# Phono-v1.net
KiCad netlist of a schematic drawn in EAGLE
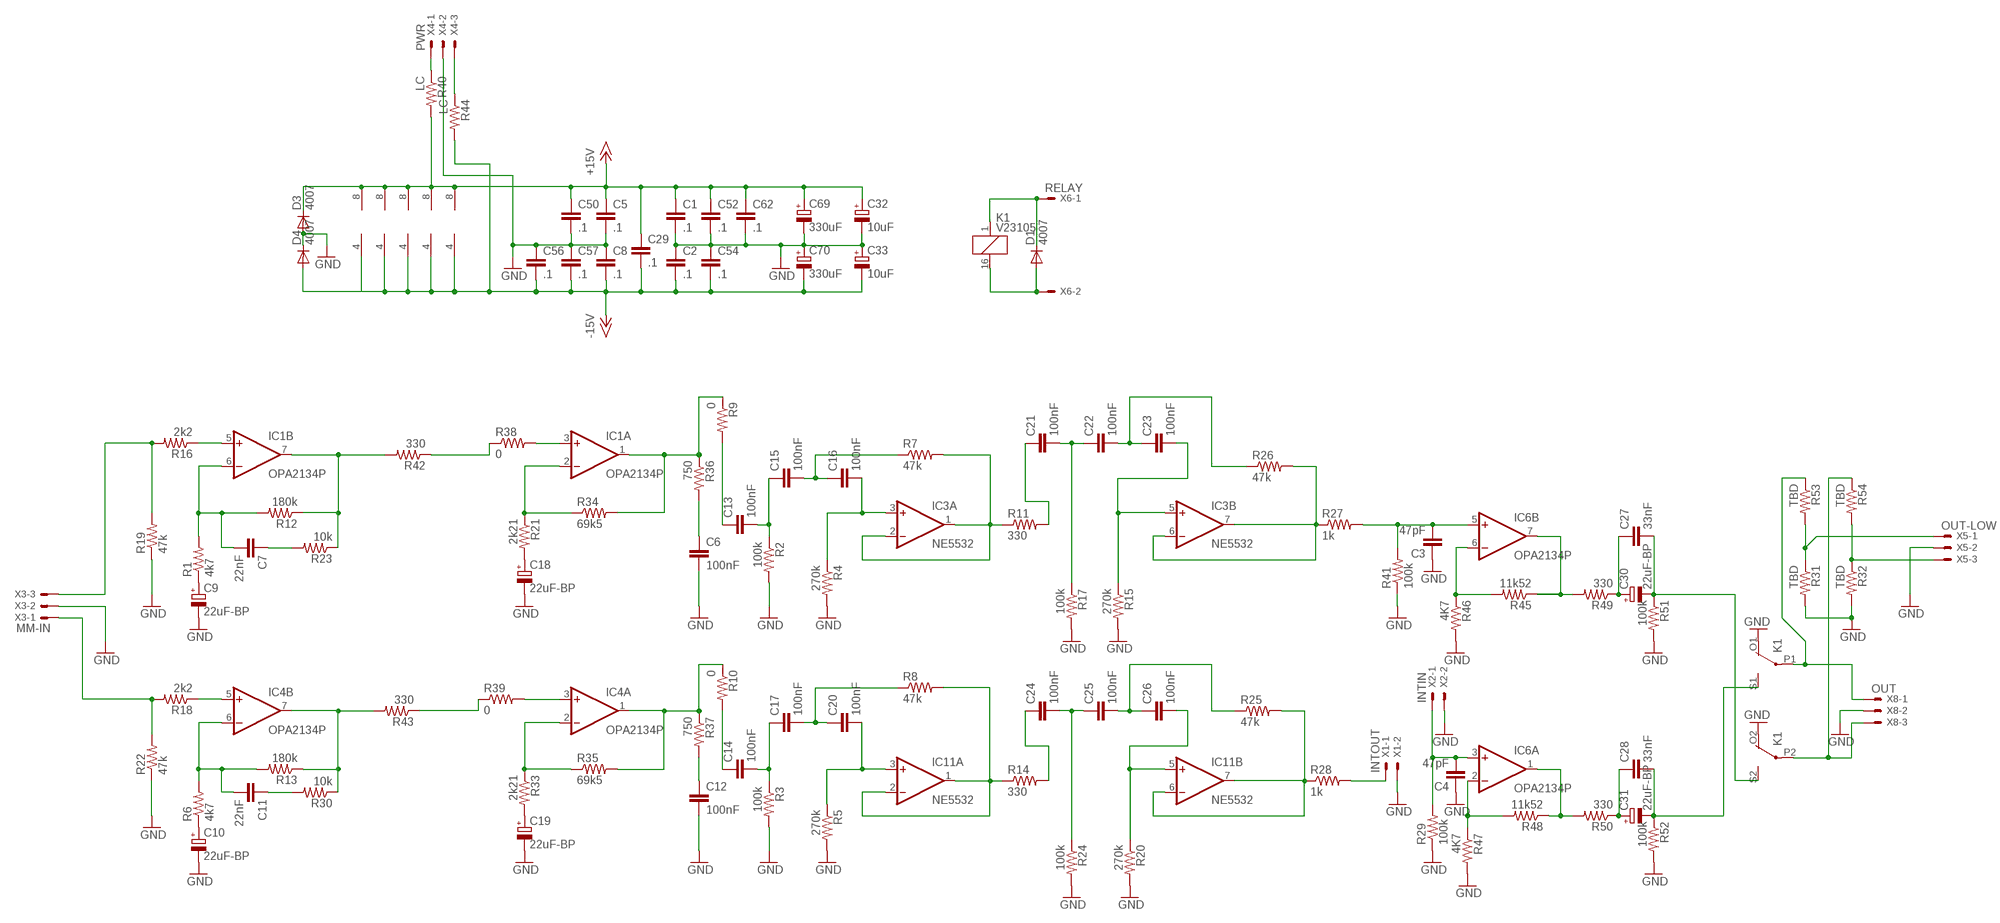
[diagram p0: schematic, sheet 1]

(export (version "E")
  (design (tool "Eeschema 10.0.6"))
  (components
    (comp (ref "C1")
      (value ".1")
      (footprint "eagle-import:C4532")
      (libsource (lib "eagle-import") (part "C-EUC4532"))
    )
    (comp (ref "C2")
      (value ".1")
      (footprint "eagle-import:C4532")
      (libsource (lib "eagle-import") (part "C-EUC4532"))
    )
    (comp (ref "C3")
      (value "47pF")
      (footprint "eagle-import:C1210")
      (libsource (lib "eagle-import") (part "C-EUC1210"))
    )
    (comp (ref "C4")
      (value "47pF")
      (footprint "eagle-import:C1210")
      (libsource (lib "eagle-import") (part "C-EUC1210"))
    )
    (comp (ref "C5")
      (value ".1")
      (footprint "eagle-import:C4532")
      (libsource (lib "eagle-import") (part "C-EUC4532"))
    )
    (comp (ref "C6")
      (value "100nF")
      (footprint "eagle-import:C050-075X075")
      (libsource (lib "eagle-import") (part "C-EU050-075X075"))
    )
    (comp (ref "C7")
      (value "22nF")
      (footprint "eagle-import:C050-075X075")
      (libsource (lib "eagle-import") (part "C-EU050-075X075"))
    )
    (comp (ref "C8")
      (value ".1")
      (footprint "eagle-import:C4532")
      (libsource (lib "eagle-import") (part "C-EUC4532"))
    )
    (comp (ref "C9")
      (value "22uF-BP")
      (footprint "eagle-import:E5-10,5")
      (libsource (lib "eagle-import") (part "CPOL-EUE5-10.5"))
    )
    (comp (ref "C10")
      (value "22uF-BP")
      (footprint "eagle-import:E5-10,5")
      (libsource (lib "eagle-import") (part "CPOL-EUE5-10.5"))
    )
    (comp (ref "C11")
      (value "22nF")
      (footprint "eagle-import:C050-075X075")
      (libsource (lib "eagle-import") (part "C-EU050-075X075"))
    )
    (comp (ref "C12")
      (value "100nF")
      (footprint "eagle-import:C050-075X075")
      (libsource (lib "eagle-import") (part "C-EU050-075X075"))
    )
    (comp (ref "C13")
      (value "100nF")
      (footprint "eagle-import:C050-075X075")
      (libsource (lib "eagle-import") (part "C-EU050-075X075"))
    )
    (comp (ref "C14")
      (value "100nF")
      (footprint "eagle-import:C050-075X075")
      (libsource (lib "eagle-import") (part "C-EU050-075X075"))
    )
    (comp (ref "C15")
      (value "100nF")
      (footprint "eagle-import:C050-075X075")
      (libsource (lib "eagle-import") (part "C-EU050-075X075"))
    )
    (comp (ref "C16")
      (value "100nF")
      (footprint "eagle-import:C050-075X075")
      (libsource (lib "eagle-import") (part "C-EU050-075X075"))
    )
    (comp (ref "C17")
      (value "100nF")
      (footprint "eagle-import:C050-075X075")
      (libsource (lib "eagle-import") (part "C-EU050-075X075"))
    )
    (comp (ref "C18")
      (value "22uF-BP")
      (footprint "eagle-import:E5-10,5")
      (libsource (lib "eagle-import") (part "CPOL-EUE5-10.5"))
    )
    (comp (ref "C19")
      (value "22uF-BP")
      (footprint "eagle-import:E5-10,5")
      (libsource (lib "eagle-import") (part "CPOL-EUE5-10.5"))
    )
    (comp (ref "C20")
      (value "100nF")
      (footprint "eagle-import:C050-075X075")
      (libsource (lib "eagle-import") (part "C-EU050-075X075"))
    )
    (comp (ref "C21")
      (value "100nF")
      (footprint "eagle-import:C050-075X075")
      (libsource (lib "eagle-import") (part "C-EU050-075X075"))
    )
    (comp (ref "C22")
      (value "100nF")
      (footprint "eagle-import:C050-075X075")
      (libsource (lib "eagle-import") (part "C-EU050-075X075"))
    )
    (comp (ref "C23")
      (value "100nF")
      (footprint "eagle-import:C050-075X075")
      (libsource (lib "eagle-import") (part "C-EU050-075X075"))
    )
    (comp (ref "C24")
      (value "100nF")
      (footprint "eagle-import:C050-075X075")
      (libsource (lib "eagle-import") (part "C-EU050-075X075"))
    )
    (comp (ref "C25")
      (value "100nF")
      (footprint "eagle-import:C050-075X075")
      (libsource (lib "eagle-import") (part "C-EU050-075X075"))
    )
    (comp (ref "C26")
      (value "100nF")
      (footprint "eagle-import:C050-075X075")
      (libsource (lib "eagle-import") (part "C-EU050-075X075"))
    )
    (comp (ref "C27")
      (value "33nF")
      (footprint "eagle-import:C050-075X075")
      (libsource (lib "eagle-import") (part "C-EU050-075X075"))
    )
    (comp (ref "C28")
      (value "33nF")
      (footprint "eagle-import:C050-075X075")
      (libsource (lib "eagle-import") (part "C-EU050-075X075"))
    )
    (comp (ref "C29")
      (value ".1")
      (footprint "eagle-import:C4532")
      (libsource (lib "eagle-import") (part "C-EUC4532"))
    )
    (comp (ref "C30")
      (value "22uF-BP")
      (footprint "eagle-import:E5-10,5")
      (libsource (lib "eagle-import") (part "CPOL-EUE5-10.5"))
    )
    (comp (ref "C31")
      (value "22uF-BP")
      (footprint "eagle-import:E5-10,5")
      (libsource (lib "eagle-import") (part "CPOL-EUE5-10.5"))
    )
    (comp (ref "C32")
      (value "10uF")
      (footprint "eagle-import:E2-5")
      (libsource (lib "eagle-import") (part "CPOL-EUE2-5"))
    )
    (comp (ref "C33")
      (value "10uF")
      (footprint "eagle-import:E2-5")
      (libsource (lib "eagle-import") (part "CPOL-EUE2-5"))
    )
    (comp (ref "C50")
      (value ".1")
      (footprint "eagle-import:C4532")
      (libsource (lib "eagle-import") (part "C-EUC4532"))
    )
    (comp (ref "C52")
      (value ".1")
      (footprint "eagle-import:C4532")
      (libsource (lib "eagle-import") (part "C-EUC4532"))
    )
    (comp (ref "C54")
      (value ".1")
      (footprint "eagle-import:C4532")
      (libsource (lib "eagle-import") (part "C-EUC4532"))
    )
    (comp (ref "C56")
      (value ".1")
      (footprint "eagle-import:C4532")
      (libsource (lib "eagle-import") (part "C-EUC4532"))
    )
    (comp (ref "C57")
      (value ".1")
      (footprint "eagle-import:C4532")
      (libsource (lib "eagle-import") (part "C-EUC4532"))
    )
    (comp (ref "C62")
      (value ".1")
      (footprint "eagle-import:C4532")
      (libsource (lib "eagle-import") (part "C-EUC4532"))
    )
    (comp (ref "C69")
      (value "330uF")
      (footprint "eagle-import:E5-10,5")
      (libsource (lib "eagle-import") (part "CPOL-EUE5-10.5"))
    )
    (comp (ref "C70")
      (value "330uF")
      (footprint "eagle-import:E5-10,5")
      (libsource (lib "eagle-import") (part "CPOL-EUE5-10.5"))
    )
    (comp (ref "D1")
      (value "4007")
      (footprint "eagle-import:DO35-7")
      (libsource (lib "eagle-import") (part "1N4148DO35-7"))
    )
    (comp (ref "D3")
      (value "4007")
      (footprint "eagle-import:DO35-10")
      (libsource (lib "eagle-import") (part "1N4148DO35-10"))
    )
    (comp (ref "D4")
      (value "4007")
      (footprint "eagle-import:DO35-10")
      (libsource (lib "eagle-import") (part "1N4148DO35-10"))
    )
    (comp (ref "IC1")
      (value "OPA2134P")
      (footprint "eagle-import:DIL08")
      (libsource (lib "eagle-import") (part "OPA2134P"))
    )
    (comp (ref "IC3")
      (value "NE5532")
      (footprint "eagle-import:DIL08")
      (libsource (lib "eagle-import") (part "OPA2134P"))
    )
    (comp (ref "IC4")
      (value "OPA2134P")
      (footprint "eagle-import:DIL08")
      (libsource (lib "eagle-import") (part "OPA2134P"))
    )
    (comp (ref "IC6")
      (value "OPA2134P")
      (footprint "eagle-import:DIL08")
      (libsource (lib "eagle-import") (part "OPA2134P"))
    )
    (comp (ref "IC11")
      (value "NE5532")
      (footprint "eagle-import:DIL08")
      (libsource (lib "eagle-import") (part "OPA2134P"))
    )
    (comp (ref "K1")
      (value "V23105")
      (footprint "eagle-import:351")
      (libsource (lib "eagle-import") (part "351"))
    )
    (comp (ref "R1")
      (value "4k7")
      (footprint "eagle-import:0309_10")
      (libsource (lib "eagle-import") (part "R-US_0309/10"))
    )
    (comp (ref "R2")
      (value "100k")
      (footprint "eagle-import:0309_10")
      (libsource (lib "eagle-import") (part "R-US_0309/10"))
    )
    (comp (ref "R3")
      (value "100k")
      (footprint "eagle-import:0309_10")
      (libsource (lib "eagle-import") (part "R-US_0309/10"))
    )
    (comp (ref "R4")
      (value "270k")
      (footprint "eagle-import:0309_10")
      (libsource (lib "eagle-import") (part "R-US_0309/10"))
    )
    (comp (ref "R5")
      (value "270k")
      (footprint "eagle-import:0309_10")
      (libsource (lib "eagle-import") (part "R-US_0309/10"))
    )
    (comp (ref "R6")
      (value "4k7")
      (footprint "eagle-import:0309_10")
      (libsource (lib "eagle-import") (part "R-US_0309/10"))
    )
    (comp (ref "R7")
      (value "47k")
      (footprint "eagle-import:0309_10")
      (libsource (lib "eagle-import") (part "R-US_0309/10"))
    )
    (comp (ref "R8")
      (value "47k")
      (footprint "eagle-import:0309_10")
      (libsource (lib "eagle-import") (part "R-US_0309/10"))
    )
    (comp (ref "R9")
      (value "0")
      (footprint "eagle-import:0309_10")
      (libsource (lib "eagle-import") (part "R-US_0309/10"))
    )
    (comp (ref "R10")
      (value "0")
      (footprint "eagle-import:0309_12")
      (libsource (lib "eagle-import") (part "R-US_0309/12"))
    )
    (comp (ref "R11")
      (value "330")
      (footprint "eagle-import:0309_10")
      (libsource (lib "eagle-import") (part "R-US_0309/10"))
    )
    (comp (ref "R12")
      (value "180k")
      (footprint "eagle-import:0309_10")
      (libsource (lib "eagle-import") (part "R-US_0309/10"))
    )
    (comp (ref "R13")
      (value "180k")
      (footprint "eagle-import:0309_10")
      (libsource (lib "eagle-import") (part "R-US_0309/10"))
    )
    (comp (ref "R14")
      (value "330")
      (footprint "eagle-import:0309_10")
      (libsource (lib "eagle-import") (part "R-US_0309/10"))
    )
    (comp (ref "R15")
      (value "270k")
      (footprint "eagle-import:0309_10")
      (libsource (lib "eagle-import") (part "R-US_0309/10"))
    )
    (comp (ref "R16")
      (value "2k2")
      (footprint "eagle-import:0309_10")
      (libsource (lib "eagle-import") (part "R-US_0309/10"))
    )
    (comp (ref "R17")
      (value "100k")
      (footprint "eagle-import:0309_10")
      (libsource (lib "eagle-import") (part "R-US_0309/10"))
    )
    (comp (ref "R18")
      (value "2k2")
      (footprint "eagle-import:0309_10")
      (libsource (lib "eagle-import") (part "R-US_0309/10"))
    )
    (comp (ref "R19")
      (value "47k")
      (footprint "eagle-import:0309_10")
      (libsource (lib "eagle-import") (part "R-US_0309/10"))
    )
    (comp (ref "R20")
      (value "270k")
      (footprint "eagle-import:0309_10")
      (libsource (lib "eagle-import") (part "R-US_0309/10"))
    )
    (comp (ref "R21")
      (value "2k21")
      (footprint "eagle-import:0309_10")
      (libsource (lib "eagle-import") (part "R-US_0309/10"))
    )
    (comp (ref "R22")
      (value "47k")
      (footprint "eagle-import:0309_10")
      (libsource (lib "eagle-import") (part "R-US_0309/10"))
    )
    (comp (ref "R23")
      (value "10k")
      (footprint "eagle-import:0309_10")
      (libsource (lib "eagle-import") (part "R-US_0309/10"))
    )
    (comp (ref "R24")
      (value "100k")
      (footprint "eagle-import:0309_10")
      (libsource (lib "eagle-import") (part "R-US_0309/10"))
    )
    (comp (ref "R25")
      (value "47k")
      (footprint "eagle-import:0309_10")
      (libsource (lib "eagle-import") (part "R-US_0309/10"))
    )
    (comp (ref "R26")
      (value "47k")
      (footprint "eagle-import:0309_10")
      (libsource (lib "eagle-import") (part "R-US_0309/10"))
    )
    (comp (ref "R27")
      (value "1k")
      (footprint "eagle-import:0309_10")
      (libsource (lib "eagle-import") (part "R-US_0309/10"))
    )
    (comp (ref "R28")
      (value "1k")
      (footprint "eagle-import:0309_12")
      (libsource (lib "eagle-import") (part "R-US_0309/12"))
    )
    (comp (ref "R29")
      (value "100k")
      (footprint "eagle-import:0309_10")
      (libsource (lib "eagle-import") (part "R-US_0309/10"))
    )
    (comp (ref "R30")
      (value "10k")
      (footprint "eagle-import:0309_10")
      (libsource (lib "eagle-import") (part "R-US_0309/10"))
    )
    (comp (ref "R31")
      (value "TBD")
      (footprint "eagle-import:0309_10")
      (libsource (lib "eagle-import") (part "R-US_0309/10"))
    )
    (comp (ref "R32")
      (value "TBD")
      (footprint "eagle-import:0309_10")
      (libsource (lib "eagle-import") (part "R-US_0309/10"))
    )
    (comp (ref "R33")
      (value "2k21")
      (footprint "eagle-import:0309_10")
      (libsource (lib "eagle-import") (part "R-US_0309/10"))
    )
    (comp (ref "R34")
      (value "69k5")
      (footprint "eagle-import:0309_10")
      (libsource (lib "eagle-import") (part "R-US_0309/10"))
    )
    (comp (ref "R35")
      (value "69k5")
      (footprint "eagle-import:0309_10")
      (libsource (lib "eagle-import") (part "R-US_0309/10"))
    )
    (comp (ref "R36")
      (value "750")
      (footprint "eagle-import:0309_10")
      (libsource (lib "eagle-import") (part "R-US_0309/10"))
    )
    (comp (ref "R37")
      (value "750")
      (footprint "eagle-import:0309_10")
      (libsource (lib "eagle-import") (part "R-US_0309/10"))
    )
    (comp (ref "R38")
      (value "0")
      (footprint "eagle-import:0207_7")
      (libsource (lib "eagle-import") (part "R-US_0207/7"))
    )
    (comp (ref "R39")
      (value "0")
      (footprint "eagle-import:0204_7")
      (libsource (lib "eagle-import") (part "R-US_0204/7"))
    )
    (comp (ref "R40")
      (value "LC")
      (footprint "eagle-import:0309_12")
      (libsource (lib "eagle-import") (part "R-US_0309/12"))
    )
    (comp (ref "R41")
      (value "100k")
      (footprint "eagle-import:0309_10")
      (libsource (lib "eagle-import") (part "R-US_0309/10"))
    )
    (comp (ref "R42")
      (value "330")
      (footprint "eagle-import:0309_10")
      (libsource (lib "eagle-import") (part "R-US_0309/10"))
    )
    (comp (ref "R43")
      (value "330")
      (footprint "eagle-import:0309_10")
      (libsource (lib "eagle-import") (part "R-US_0309/10"))
    )
    (comp (ref "R44")
      (value "LC")
      (footprint "eagle-import:0309_12")
      (libsource (lib "eagle-import") (part "R-US_0309/12"))
    )
    (comp (ref "R45")
      (value "11k52")
      (footprint "eagle-import:0309_10")
      (libsource (lib "eagle-import") (part "R-US_0309/10"))
    )
    (comp (ref "R46")
      (value "4K7")
      (footprint "eagle-import:0309_10")
      (libsource (lib "eagle-import") (part "R-US_0309/10"))
    )
    (comp (ref "R47")
      (value "4K7")
      (footprint "eagle-import:0309_10")
      (libsource (lib "eagle-import") (part "R-US_0309/10"))
    )
    (comp (ref "R48")
      (value "11k52")
      (footprint "eagle-import:0309_10")
      (libsource (lib "eagle-import") (part "R-US_0309/10"))
    )
    (comp (ref "R49")
      (value "330")
      (footprint "eagle-import:0309_10")
      (libsource (lib "eagle-import") (part "R-US_0309/10"))
    )
    (comp (ref "R50")
      (value "330")
      (footprint "eagle-import:0309_10")
      (libsource (lib "eagle-import") (part "R-US_0309/10"))
    )
    (comp (ref "R51")
      (value "100k")
      (footprint "eagle-import:0309_10")
      (libsource (lib "eagle-import") (part "R-US_0309/10"))
    )
    (comp (ref "R52")
      (value "100k")
      (footprint "eagle-import:0309_10")
      (libsource (lib "eagle-import") (part "R-US_0309/10"))
    )
    (comp (ref "R53")
      (value "TBD")
      (footprint "eagle-import:0309_10")
      (libsource (lib "eagle-import") (part "R-US_0309/10"))
    )
    (comp (ref "R54")
      (value "TBD")
      (footprint "eagle-import:0309_10")
      (libsource (lib "eagle-import") (part "R-US_0309/10"))
    )
    (comp (ref "X1")
      (value "INTOUT")
      (footprint "eagle-import:22-23-2021")
      (fields (field (name "MF") "MOLEX") (field (name "MPN") "22-23-2021"))
      (libsource (lib "eagle-import") (part "22-23-2021"))
    )
    (comp (ref "X2")
      (value "INTIN")
      (footprint "eagle-import:22-23-2021")
      (fields (field (name "MF") "MOLEX") (field (name "MPN") "22-23-2021"))
      (libsource (lib "eagle-import") (part "22-23-2021"))
    )
    (comp (ref "X3")
      (value "MM-IN")
      (footprint "eagle-import:22-23-2031")
      (fields (field (name "MF") "MOLEX") (field (name "MPN") "22-23-2031"))
      (libsource (lib "eagle-import") (part "22-23-2031"))
    )
    (comp (ref "X4")
      (value "PWR")
      (footprint "eagle-import:22-23-2031")
      (fields (field (name "MF") "MOLEX") (field (name "MPN") "22-23-2031"))
      (libsource (lib "eagle-import") (part "22-23-2031"))
    )
    (comp (ref "X5")
      (value "OUT-LOW")
      (footprint "eagle-import:22-23-2031")
      (fields (field (name "MF") "MOLEX") (field (name "MPN") "22-23-2031"))
      (libsource (lib "eagle-import") (part "22-23-2031"))
    )
    (comp (ref "X6")
      (value "RELAY")
      (footprint "eagle-import:22-23-2021")
      (fields (field (name "MF") "MOLEX") (field (name "MPN") "22-23-2021"))
      (libsource (lib "eagle-import") (part "22-23-2021"))
    )
    (comp (ref "X8")
      (value "OUT")
      (footprint "eagle-import:22-23-2031")
      (fields (field (name "MF") "MOLEX") (field (name "MPN") "22-23-2031"))
      (libsource (lib "eagle-import") (part "22-23-2031"))
    )
  )
  (nets
    (net (code "1") (name "+15V") (class "Default")
      (node (ref "C1") (pin "1") (pinfunction "1_1") (pintype "passive"))
      (node (ref "C29") (pin "1") (pinfunction "1_1") (pintype "passive"))
      (node (ref "C32") (pin "+") (pinfunction "+_+") (pintype "passive"))
      (node (ref "C5") (pin "1") (pinfunction "1_1") (pintype "passive"))
      (node (ref "C50") (pin "1") (pinfunction "1_1") (pintype "passive"))
      (node (ref "C52") (pin "1") (pinfunction "1_1") (pintype "passive"))
      (node (ref "C62") (pin "1") (pinfunction "1_1") (pintype "passive"))
      (node (ref "C69") (pin "+") (pinfunction "+_+") (pintype "passive"))
      (node (ref "D3") (pin "C") (pinfunction "C_C") (pintype "passive"))
      (node (ref "IC1") (pin "8") (pinfunction "V+_8") (pintype "power_in"))
      (node (ref "IC11") (pin "8") (pinfunction "V+_8") (pintype "power_in"))
      (node (ref "IC3") (pin "8") (pinfunction "V+_8") (pintype "power_in"))
      (node (ref "IC4") (pin "8") (pinfunction "V+_8") (pintype "power_in"))
      (node (ref "IC6") (pin "8") (pinfunction "V+_8") (pintype "power_in"))
      (node (ref "R40") (pin "2") (pinfunction "2_2") (pintype "passive"))
    )
    (net (code "2") (name "-15V") (class "Default")
      (node (ref "C2") (pin "2") (pinfunction "2_2") (pintype "passive"))
      (node (ref "C29") (pin "2") (pinfunction "2_2") (pintype "passive"))
      (node (ref "C33") (pin "-") (pinfunction "-_-") (pintype "passive"))
      (node (ref "C54") (pin "2") (pinfunction "2_2") (pintype "passive"))
      (node (ref "C56") (pin "2") (pinfunction "2_2") (pintype "passive"))
      (node (ref "C57") (pin "2") (pinfunction "2_2") (pintype "passive"))
      (node (ref "C70") (pin "-") (pinfunction "-_-") (pintype "passive"))
      (node (ref "C8") (pin "2") (pinfunction "2_2") (pintype "passive"))
      (node (ref "D4") (pin "A") (pinfunction "A_A") (pintype "passive"))
      (node (ref "IC1") (pin "4") (pinfunction "V-_4") (pintype "power_in"))
      (node (ref "IC11") (pin "4") (pinfunction "V-_4") (pintype "power_in"))
      (node (ref "IC3") (pin "4") (pinfunction "V-_4") (pintype "power_in"))
      (node (ref "IC4") (pin "4") (pinfunction "V-_4") (pintype "power_in"))
      (node (ref "IC6") (pin "4") (pinfunction "V-_4") (pintype "power_in"))
      (node (ref "R44") (pin "2") (pinfunction "2_2") (pintype "passive"))
    )
    (net (code "3") (name "GND") (class "Default")
      (node (ref "C1") (pin "2") (pinfunction "2_2") (pintype "passive"))
      (node (ref "C10") (pin "-") (pinfunction "-_-") (pintype "passive"))
      (node (ref "C12") (pin "2") (pinfunction "2_2") (pintype "passive"))
      (node (ref "C18") (pin "-") (pinfunction "-_-") (pintype "passive"))
      (node (ref "C19") (pin "-") (pinfunction "-_-") (pintype "passive"))
      (node (ref "C2") (pin "1") (pinfunction "1_1") (pintype "passive"))
      (node (ref "C3") (pin "1") (pinfunction "1_1") (pintype "passive"))
      (node (ref "C32") (pin "-") (pinfunction "-_-") (pintype "passive"))
      (node (ref "C33") (pin "+") (pinfunction "+_+") (pintype "passive"))
      (node (ref "C4") (pin "1") (pinfunction "1_1") (pintype "passive"))
      (node (ref "C5") (pin "2") (pinfunction "2_2") (pintype "passive"))
      (node (ref "C50") (pin "2") (pinfunction "2_2") (pintype "passive"))
      (node (ref "C52") (pin "2") (pinfunction "2_2") (pintype "passive"))
      (node (ref "C54") (pin "1") (pinfunction "1_1") (pintype "passive"))
      (node (ref "C56") (pin "1") (pinfunction "1_1") (pintype "passive"))
      (node (ref "C57") (pin "1") (pinfunction "1_1") (pintype "passive"))
      (node (ref "C6") (pin "2") (pinfunction "2_2") (pintype "passive"))
      (node (ref "C62") (pin "2") (pinfunction "2_2") (pintype "passive"))
      (node (ref "C69") (pin "-") (pinfunction "-_-") (pintype "passive"))
      (node (ref "C70") (pin "+") (pinfunction "+_+") (pintype "passive"))
      (node (ref "C8") (pin "1") (pinfunction "1_1") (pintype "passive"))
      (node (ref "C9") (pin "-") (pinfunction "-_-") (pintype "passive"))
      (node (ref "D3") (pin "A") (pinfunction "A_A") (pintype "passive"))
      (node (ref "D4") (pin "C") (pinfunction "C_C") (pintype "passive"))
      (node (ref "K1") (pin "O1") (pinfunction "O_O1") (pintype "passive"))
      (node (ref "K1") (pin "O2") (pinfunction "O_O2") (pintype "passive"))
      (node (ref "R15") (pin "2") (pinfunction "2_2") (pintype "passive"))
      (node (ref "R17") (pin "2") (pinfunction "2_2") (pintype "passive"))
      (node (ref "R19") (pin "1") (pinfunction "1_1") (pintype "passive"))
      (node (ref "R2") (pin "2") (pinfunction "2_2") (pintype "passive"))
      (node (ref "R20") (pin "2") (pinfunction "2_2") (pintype "passive"))
      (node (ref "R22") (pin "1") (pinfunction "1_1") (pintype "passive"))
      (node (ref "R24") (pin "2") (pinfunction "2_2") (pintype "passive"))
      (node (ref "R29") (pin "1") (pinfunction "1_1") (pintype "passive"))
      (node (ref "R3") (pin "2") (pinfunction "2_2") (pintype "passive"))
      (node (ref "R31") (pin "2") (pinfunction "2_2") (pintype "passive"))
      (node (ref "R32") (pin "2") (pinfunction "2_2") (pintype "passive"))
      (node (ref "R4") (pin "2") (pinfunction "2_2") (pintype "passive"))
      (node (ref "R41") (pin "1") (pinfunction "1_1") (pintype "passive"))
      (node (ref "R46") (pin "2") (pinfunction "2_2") (pintype "passive"))
      (node (ref "R47") (pin "2") (pinfunction "2_2") (pintype "passive"))
      (node (ref "R5") (pin "2") (pinfunction "2_2") (pintype "passive"))
      (node (ref "R51") (pin "2") (pinfunction "2_2") (pintype "passive"))
      (node (ref "R52") (pin "2") (pinfunction "2_2") (pintype "passive"))
      (node (ref "X1") (pin "2") (pinfunction "S_2") (pintype "passive"))
      (node (ref "X2") (pin "2") (pinfunction "S_2") (pintype "passive"))
      (node (ref "X3") (pin "2") (pinfunction "S_2") (pintype "passive"))
      (node (ref "X4") (pin "2") (pinfunction "S_2") (pintype "passive"))
      (node (ref "X5") (pin "2") (pinfunction "S_2") (pintype "passive"))
      (node (ref "X8") (pin "2") (pinfunction "S_2") (pintype "passive"))
    )
    (net (code "4") (name "Net-(C6-Pad1)") (class "Default")
      (node (ref "C6") (pin "1") (pinfunction "1_1") (pintype "passive"))
      (node (ref "R36") (pin "2") (pinfunction "2_2") (pintype "passive"))
    )
    (net (code "5") (name "Net-(C7-Pad1)") (class "Default")
      (node (ref "C7") (pin "1") (pinfunction "1_1") (pintype "passive"))
      (node (ref "R23") (pin "2") (pinfunction "2_2") (pintype "passive"))
    )
    (net (code "6") (name "Net-(C9-Pad+)") (class "Default")
      (node (ref "C9") (pin "+") (pinfunction "+_+") (pintype "passive"))
      (node (ref "R1") (pin "1") (pinfunction "1_1") (pintype "passive"))
    )
    (net (code "7") (name "Net-(C10-Pad+)") (class "Default")
      (node (ref "C10") (pin "+") (pinfunction "+_+") (pintype "passive"))
      (node (ref "R6") (pin "1") (pinfunction "1_1") (pintype "passive"))
    )
    (net (code "8") (name "Net-(C11-Pad1)") (class "Default")
      (node (ref "C11") (pin "1") (pinfunction "1_1") (pintype "passive"))
      (node (ref "R30") (pin "2") (pinfunction "2_2") (pintype "passive"))
    )
    (net (code "9") (name "Net-(C12-Pad1)") (class "Default")
      (node (ref "C12") (pin "1") (pinfunction "1_1") (pintype "passive"))
      (node (ref "R37") (pin "2") (pinfunction "2_2") (pintype "passive"))
    )
    (net (code "10") (name "Net-(C13-Pad1)") (class "Default")
      (node (ref "C13") (pin "1") (pinfunction "1_1") (pintype "passive"))
      (node (ref "R9") (pin "2") (pinfunction "2_2") (pintype "passive"))
    )
    (net (code "11") (name "Net-(C13-Pad2)") (class "Default")
      (node (ref "C13") (pin "2") (pinfunction "2_2") (pintype "passive"))
      (node (ref "C15") (pin "1") (pinfunction "1_1") (pintype "passive"))
      (node (ref "R2") (pin "1") (pinfunction "1_1") (pintype "passive"))
    )
    (net (code "12") (name "Net-(C14-Pad1)") (class "Default")
      (node (ref "C14") (pin "1") (pinfunction "1_1") (pintype "passive"))
      (node (ref "R10") (pin "2") (pinfunction "2_2") (pintype "passive"))
    )
    (net (code "13") (name "Net-(C14-Pad2)") (class "Default")
      (node (ref "C14") (pin "2") (pinfunction "2_2") (pintype "passive"))
      (node (ref "C17") (pin "1") (pinfunction "1_1") (pintype "passive"))
      (node (ref "R3") (pin "1") (pinfunction "1_1") (pintype "passive"))
    )
    (net (code "14") (name "Net-(C15-Pad2)") (class "Default")
      (node (ref "C15") (pin "2") (pinfunction "2_2") (pintype "passive"))
      (node (ref "C16") (pin "1") (pinfunction "1_1") (pintype "passive"))
      (node (ref "R7") (pin "1") (pinfunction "1_1") (pintype "passive"))
    )
    (net (code "15") (name "Net-(C17-Pad2)") (class "Default")
      (node (ref "C17") (pin "2") (pinfunction "2_2") (pintype "passive"))
      (node (ref "C20") (pin "1") (pinfunction "1_1") (pintype "passive"))
      (node (ref "R8") (pin "1") (pinfunction "1_1") (pintype "passive"))
    )
    (net (code "16") (name "Net-(C18-Pad+)") (class "Default")
      (node (ref "C18") (pin "+") (pinfunction "+_+") (pintype "passive"))
      (node (ref "R21") (pin "2") (pinfunction "2_2") (pintype "passive"))
    )
    (net (code "17") (name "Net-(C19-Pad+)") (class "Default")
      (node (ref "C19") (pin "+") (pinfunction "+_+") (pintype "passive"))
      (node (ref "R33") (pin "2") (pinfunction "2_2") (pintype "passive"))
    )
    (net (code "18") (name "Net-(C21-Pad1)") (class "Default")
      (node (ref "C21") (pin "1") (pinfunction "1_1") (pintype "passive"))
      (node (ref "R11") (pin "2") (pinfunction "2_2") (pintype "passive"))
    )
    (net (code "19") (name "Net-(C21-Pad2)") (class "Default")
      (node (ref "C21") (pin "2") (pinfunction "2_2") (pintype "passive"))
      (node (ref "C22") (pin "1") (pinfunction "1_1") (pintype "passive"))
      (node (ref "R17") (pin "1") (pinfunction "1_1") (pintype "passive"))
    )
    (net (code "20") (name "Net-(C22-Pad2)") (class "Default")
      (node (ref "C22") (pin "2") (pinfunction "2_2") (pintype "passive"))
      (node (ref "C23") (pin "1") (pinfunction "1_1") (pintype "passive"))
      (node (ref "R26") (pin "1") (pinfunction "1_1") (pintype "passive"))
    )
    (net (code "21") (name "Net-(C24-Pad1)") (class "Default")
      (node (ref "C24") (pin "1") (pinfunction "1_1") (pintype "passive"))
      (node (ref "R14") (pin "2") (pinfunction "2_2") (pintype "passive"))
    )
    (net (code "22") (name "Net-(C24-Pad2)") (class "Default")
      (node (ref "C24") (pin "2") (pinfunction "2_2") (pintype "passive"))
      (node (ref "C25") (pin "1") (pinfunction "1_1") (pintype "passive"))
      (node (ref "R24") (pin "1") (pinfunction "1_1") (pintype "passive"))
    )
    (net (code "23") (name "Net-(C25-Pad2)") (class "Default")
      (node (ref "C25") (pin "2") (pinfunction "2_2") (pintype "passive"))
      (node (ref "C26") (pin "1") (pinfunction "1_1") (pintype "passive"))
      (node (ref "R25") (pin "1") (pinfunction "1_1") (pintype "passive"))
    )
    (net (code "24") (name "Net-(C27-Pad1)") (class "Default")
      (node (ref "C27") (pin "1") (pinfunction "1_1") (pintype "passive"))
      (node (ref "C30") (pin "+") (pinfunction "+_+") (pintype "passive"))
      (node (ref "R49") (pin "1") (pinfunction "1_1") (pintype "passive"))
    )
    (net (code "25") (name "Net-(C28-Pad1)") (class "Default")
      (node (ref "C28") (pin "1") (pinfunction "1_1") (pintype "passive"))
      (node (ref "C31") (pin "+") (pinfunction "+_+") (pintype "passive"))
      (node (ref "R50") (pin "1") (pinfunction "1_1") (pintype "passive"))
    )
    (net (code "26") (name "Net-(IC1A-+IN)") (class "Default")
      (node (ref "IC1") (pin "3") (pinfunction "+IN_3") (pintype "input"))
      (node (ref "R38") (pin "2") (pinfunction "2_2") (pintype "passive"))
    )
    (net (code "27") (name "Net-(IC1A--IN)") (class "Default")
      (node (ref "IC1") (pin "2") (pinfunction "-IN_2") (pintype "input"))
      (node (ref "R21") (pin "1") (pinfunction "1_1") (pintype "passive"))
      (node (ref "R34") (pin "1") (pinfunction "1_1") (pintype "passive"))
    )
    (net (code "28") (name "Net-(IC1A-OUT)") (class "Default")
      (node (ref "IC1") (pin "1") (pinfunction "OUT_1") (pintype "output"))
      (node (ref "R34") (pin "2") (pinfunction "2_2") (pintype "passive"))
      (node (ref "R36") (pin "1") (pinfunction "1_1") (pintype "passive"))
      (node (ref "R9") (pin "1") (pinfunction "1_1") (pintype "passive"))
    )
    (net (code "29") (name "Net-(IC1B-+IN)") (class "Default")
      (node (ref "IC1") (pin "5") (pinfunction "+IN_5") (pintype "input"))
      (node (ref "R16") (pin "1") (pinfunction "1_1") (pintype "passive"))
    )
    (net (code "30") (name "Net-(IC1B--IN)") (class "Default")
      (node (ref "C7") (pin "2") (pinfunction "2_2") (pintype "passive"))
      (node (ref "IC1") (pin "6") (pinfunction "-IN_6") (pintype "input"))
      (node (ref "R1") (pin "2") (pinfunction "2_2") (pintype "passive"))
      (node (ref "R12") (pin "2") (pinfunction "2_2") (pintype "passive"))
    )
    (net (code "31") (name "Net-(IC1B-OUT)") (class "Default")
      (node (ref "IC1") (pin "7") (pinfunction "OUT_7") (pintype "output"))
      (node (ref "R12") (pin "1") (pinfunction "1_1") (pintype "passive"))
      (node (ref "R23") (pin "1") (pinfunction "1_1") (pintype "passive"))
      (node (ref "R42") (pin "2") (pinfunction "2_2") (pintype "passive"))
    )
    (net (code "32") (name "Net-(IC3A-+IN)") (class "Default")
      (node (ref "C16") (pin "2") (pinfunction "2_2") (pintype "passive"))
      (node (ref "IC3") (pin "3") (pinfunction "+IN_3") (pintype "input"))
      (node (ref "R4") (pin "1") (pinfunction "1_1") (pintype "passive"))
    )
    (net (code "33") (name "Net-(IC3A--IN)") (class "Default")
      (node (ref "IC3") (pin "1") (pinfunction "OUT_1") (pintype "output"))
      (node (ref "IC3") (pin "2") (pinfunction "-IN_2") (pintype "input"))
      (node (ref "R11") (pin "1") (pinfunction "1_1") (pintype "passive"))
      (node (ref "R7") (pin "2") (pinfunction "2_2") (pintype "passive"))
    )
    (net (code "34") (name "Net-(IC3B-+IN)") (class "Default")
      (node (ref "C23") (pin "2") (pinfunction "2_2") (pintype "passive"))
      (node (ref "IC3") (pin "5") (pinfunction "+IN_5") (pintype "input"))
      (node (ref "R15") (pin "1") (pinfunction "1_1") (pintype "passive"))
    )
    (net (code "35") (name "Net-(IC3B--IN)") (class "Default")
      (node (ref "IC3") (pin "6") (pinfunction "-IN_6") (pintype "input"))
      (node (ref "IC3") (pin "7") (pinfunction "OUT_7") (pintype "output"))
      (node (ref "R26") (pin "2") (pinfunction "2_2") (pintype "passive"))
      (node (ref "R27") (pin "1") (pinfunction "1_1") (pintype "passive"))
    )
    (net (code "36") (name "Net-(IC4A-+IN)") (class "Default")
      (node (ref "IC4") (pin "3") (pinfunction "+IN_3") (pintype "input"))
      (node (ref "R39") (pin "2") (pinfunction "2_2") (pintype "passive"))
    )
    (net (code "37") (name "Net-(IC4A--IN)") (class "Default")
      (node (ref "IC4") (pin "2") (pinfunction "-IN_2") (pintype "input"))
      (node (ref "R33") (pin "1") (pinfunction "1_1") (pintype "passive"))
      (node (ref "R35") (pin "1") (pinfunction "1_1") (pintype "passive"))
    )
    (net (code "38") (name "Net-(IC4A-OUT)") (class "Default")
      (node (ref "IC4") (pin "1") (pinfunction "OUT_1") (pintype "output"))
      (node (ref "R10") (pin "1") (pinfunction "1_1") (pintype "passive"))
      (node (ref "R35") (pin "2") (pinfunction "2_2") (pintype "passive"))
      (node (ref "R37") (pin "1") (pinfunction "1_1") (pintype "passive"))
    )
    (net (code "39") (name "Net-(IC4B-+IN)") (class "Default")
      (node (ref "IC4") (pin "5") (pinfunction "+IN_5") (pintype "input"))
      (node (ref "R18") (pin "1") (pinfunction "1_1") (pintype "passive"))
    )
    (net (code "40") (name "Net-(IC4B--IN)") (class "Default")
      (node (ref "C11") (pin "2") (pinfunction "2_2") (pintype "passive"))
      (node (ref "IC4") (pin "6") (pinfunction "-IN_6") (pintype "input"))
      (node (ref "R13") (pin "2") (pinfunction "2_2") (pintype "passive"))
      (node (ref "R6") (pin "2") (pinfunction "2_2") (pintype "passive"))
    )
    (net (code "41") (name "Net-(IC4B-OUT)") (class "Default")
      (node (ref "IC4") (pin "7") (pinfunction "OUT_7") (pintype "output"))
      (node (ref "R13") (pin "1") (pinfunction "1_1") (pintype "passive"))
      (node (ref "R30") (pin "1") (pinfunction "1_1") (pintype "passive"))
      (node (ref "R43") (pin "2") (pinfunction "2_2") (pintype "passive"))
    )
    (net (code "42") (name "Net-(IC6A-+IN)") (class "Default")
      (node (ref "C4") (pin "2") (pinfunction "2_2") (pintype "passive"))
      (node (ref "IC6") (pin "3") (pinfunction "+IN_3") (pintype "input"))
      (node (ref "R29") (pin "2") (pinfunction "2_2") (pintype "passive"))
      (node (ref "X2") (pin "1") (pinfunction "S_1") (pintype "passive"))
    )
    (net (code "43") (name "Net-(IC6A--IN)") (class "Default")
      (node (ref "IC6") (pin "2") (pinfunction "-IN_2") (pintype "input"))
      (node (ref "R47") (pin "1") (pinfunction "1_1") (pintype "passive"))
      (node (ref "R48") (pin "2") (pinfunction "2_2") (pintype "passive"))
    )
    (net (code "44") (name "Net-(IC6A-OUT)") (class "Default")
      (node (ref "IC6") (pin "1") (pinfunction "OUT_1") (pintype "output"))
      (node (ref "R48") (pin "1") (pinfunction "1_1") (pintype "passive"))
      (node (ref "R50") (pin "2") (pinfunction "2_2") (pintype "passive"))
    )
    (net (code "45") (name "Net-(IC6B-+IN)") (class "Default")
      (node (ref "C3") (pin "2") (pinfunction "2_2") (pintype "passive"))
      (node (ref "IC6") (pin "5") (pinfunction "+IN_5") (pintype "input"))
      (node (ref "R27") (pin "2") (pinfunction "2_2") (pintype "passive"))
      (node (ref "R41") (pin "2") (pinfunction "2_2") (pintype "passive"))
    )
    (net (code "46") (name "Net-(IC6B--IN)") (class "Default")
      (node (ref "IC6") (pin "6") (pinfunction "-IN_6") (pintype "input"))
      (node (ref "R45") (pin "2") (pinfunction "2_2") (pintype "passive"))
      (node (ref "R46") (pin "1") (pinfunction "1_1") (pintype "passive"))
    )
    (net (code "47") (name "Net-(IC6B-OUT)") (class "Default")
      (node (ref "IC6") (pin "7") (pinfunction "OUT_7") (pintype "output"))
      (node (ref "R45") (pin "1") (pinfunction "1_1") (pintype "passive"))
      (node (ref "R49") (pin "2") (pinfunction "2_2") (pintype "passive"))
    )
    (net (code "48") (name "Net-(IC11A-+IN)") (class "Default")
      (node (ref "C20") (pin "2") (pinfunction "2_2") (pintype "passive"))
      (node (ref "IC11") (pin "3") (pinfunction "+IN_3") (pintype "input"))
      (node (ref "R5") (pin "1") (pinfunction "1_1") (pintype "passive"))
    )
    (net (code "49") (name "Net-(IC11A--IN)") (class "Default")
      (node (ref "IC11") (pin "1") (pinfunction "OUT_1") (pintype "output"))
      (node (ref "IC11") (pin "2") (pinfunction "-IN_2") (pintype "input"))
      (node (ref "R14") (pin "1") (pinfunction "1_1") (pintype "passive"))
      (node (ref "R8") (pin "2") (pinfunction "2_2") (pintype "passive"))
    )
    (net (code "50") (name "Net-(IC11B-+IN)") (class "Default")
      (node (ref "C26") (pin "2") (pinfunction "2_2") (pintype "passive"))
      (node (ref "IC11") (pin "5") (pinfunction "+IN_5") (pintype "input"))
      (node (ref "R20") (pin "1") (pinfunction "1_1") (pintype "passive"))
    )
    (net (code "51") (name "Net-(IC11B--IN)") (class "Default")
      (node (ref "IC11") (pin "6") (pinfunction "-IN_6") (pintype "input"))
      (node (ref "IC11") (pin "7") (pinfunction "OUT_7") (pintype "output"))
      (node (ref "R25") (pin "2") (pinfunction "2_2") (pintype "passive"))
      (node (ref "R28") (pin "1") (pinfunction "1_1") (pintype "passive"))
    )
    (net (code "52") (name "Net-(K1A-2)") (class "Default")
      (node (ref "D1") (pin "A") (pinfunction "A_A") (pintype "passive"))
      (node (ref "K1") (pin "16") (pinfunction "2_16") (pintype "passive"))
      (node (ref "X6") (pin "2") (pinfunction "S_2") (pintype "passive"))
    )
    (net (code "53") (name "Net-(K1B-P)") (class "Default")
      (node (ref "K1") (pin "P1") (pinfunction "P_P1") (pintype "passive"))
      (node (ref "R53") (pin "1") (pinfunction "1_1") (pintype "passive"))
      (node (ref "X8") (pin "1") (pinfunction "S_1") (pintype "passive"))
    )
    (net (code "54") (name "Net-(K1B-S)") (class "Default")
      (node (ref "C28") (pin "2") (pinfunction "2_2") (pintype "passive"))
      (node (ref "C31") (pin "-") (pinfunction "-_-") (pintype "passive"))
      (node (ref "K1") (pin "S1") (pinfunction "S_S1") (pintype "passive"))
      (node (ref "R52") (pin "1") (pinfunction "1_1") (pintype "passive"))
    )
    (net (code "55") (name "Net-(K1C-P)") (class "Default")
      (node (ref "K1") (pin "P2") (pinfunction "P_P2") (pintype "passive"))
      (node (ref "R54") (pin "1") (pinfunction "1_1") (pintype "passive"))
      (node (ref "X8") (pin "3") (pinfunction "S_3") (pintype "passive"))
    )
    (net (code "56") (name "Net-(K1C-S)") (class "Default")
      (node (ref "C27") (pin "2") (pinfunction "2_2") (pintype "passive"))
      (node (ref "C30") (pin "-") (pinfunction "-_-") (pintype "passive"))
      (node (ref "K1") (pin "S2") (pinfunction "S_S2") (pintype "passive"))
      (node (ref "R51") (pin "1") (pinfunction "1_1") (pintype "passive"))
    )
    (net (code "57") (name "Net-(R38-Pad1)") (class "Default")
      (node (ref "R38") (pin "1") (pinfunction "1_1") (pintype "passive"))
      (node (ref "R42") (pin "1") (pinfunction "1_1") (pintype "passive"))
    )
    (net (code "58") (name "Net-(R39-Pad1)") (class "Default")
      (node (ref "R39") (pin "1") (pinfunction "1_1") (pintype "passive"))
      (node (ref "R43") (pin "1") (pinfunction "1_1") (pintype "passive"))
    )
    (net (code "59") (name "Net-(X1A-S)") (class "Default")
      (node (ref "R28") (pin "2") (pinfunction "2_2") (pintype "passive"))
      (node (ref "X1") (pin "1") (pinfunction "S_1") (pintype "passive"))
    )
    (net (code "60") (name "Net-(X3A-S)") (class "Default")
      (node (ref "R18") (pin "2") (pinfunction "2_2") (pintype "passive"))
      (node (ref "R22") (pin "2") (pinfunction "2_2") (pintype "passive"))
      (node (ref "X3") (pin "1") (pinfunction "S_1") (pintype "passive"))
    )
    (net (code "61") (name "Net-(X3C-S)") (class "Default")
      (node (ref "R16") (pin "2") (pinfunction "2_2") (pintype "passive"))
      (node (ref "R19") (pin "2") (pinfunction "2_2") (pintype "passive"))
      (node (ref "X3") (pin "3") (pinfunction "S_3") (pintype "passive"))
    )
    (net (code "62") (name "Net-(X4A-S)") (class "Default")
      (node (ref "R40") (pin "1") (pinfunction "1_1") (pintype "passive"))
      (node (ref "X4") (pin "1") (pinfunction "S_1") (pintype "passive"))
    )
    (net (code "63") (name "Net-(X4C-S)") (class "Default")
      (node (ref "R44") (pin "1") (pinfunction "1_1") (pintype "passive"))
      (node (ref "X4") (pin "3") (pinfunction "S_3") (pintype "passive"))
    )
    (net (code "64") (name "Net-(X5A-S)") (class "Default")
      (node (ref "R31") (pin "1") (pinfunction "1_1") (pintype "passive"))
      (node (ref "R53") (pin "2") (pinfunction "2_2") (pintype "passive"))
      (node (ref "X5") (pin "1") (pinfunction "S_1") (pintype "passive"))
    )
    (net (code "65") (name "Net-(X5C-S)") (class "Default")
      (node (ref "R32") (pin "1") (pinfunction "1_1") (pintype "passive"))
      (node (ref "R54") (pin "2") (pinfunction "2_2") (pintype "passive"))
      (node (ref "X5") (pin "3") (pinfunction "S_3") (pintype "passive"))
    )
    (net (code "66") (name "Net-(X6A-S)") (class "Default")
      (node (ref "D1") (pin "C") (pinfunction "C_C") (pintype "passive"))
      (node (ref "K1") (pin "1") (pinfunction "1_1") (pintype "passive"))
      (node (ref "X6") (pin "1") (pinfunction "S_1") (pintype "passive"))
    )
  )
)
